# Peripheral.net
KiCad netlist of a schematic drawn in Altium Designer
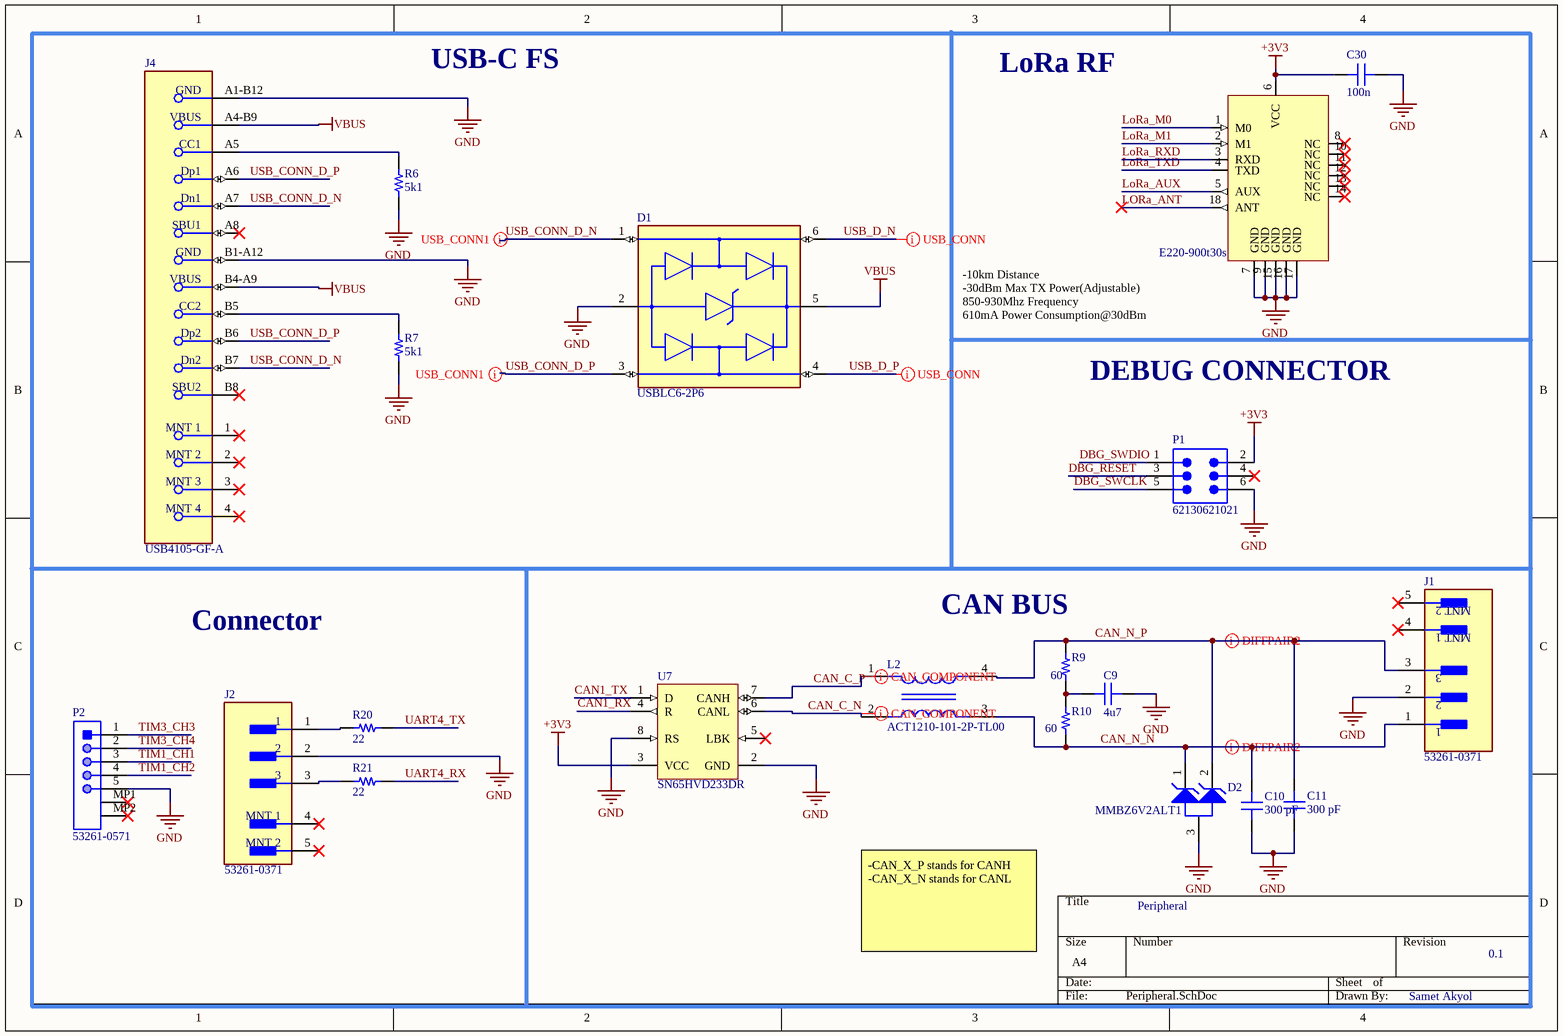
[diagram p0: Peripheral.SchDoc]

(export (version "E")
  (design (tool "Eeschema 10.0.6"))
  (components
    (comp (ref "C9")
      (value "4u7")
      (footprint "CAP 0603_1608")
      (description "CAP CER 4.7UF 25V X5R 0603")
      (fields
        (field (name "PART NUMBER") "CL10A475KA8NQNC")
        (field (name "MANUFACTURER") "Samsung Electro-Mechanics")
      )
      (libsource (lib "Celestial Altium Library - altium_library") (part "Capacitor"))
    )
    (comp (ref "C10")
      (value "300 pF")
      (footprint "CAP 0402_1005")
      (description "CAP CER 300PF 25V C0G/NP0 0402")
      (fields (field (name "PART NUMBER") "C0402C301J3GAC7867") (field (name "MANUFACTURER") "KEMET"))
      (libsource (lib "Celestial Altium Library - altium_library") (part "Capacitor"))
    )
    (comp (ref "C11")
      (value "300 pF")
      (footprint "CAP 0402_1005")
      (description "CAP CER 300PF 25V C0G/NP0 0402")
      (fields (field (name "PART NUMBER") "C0402C301J3GAC7867") (field (name "MANUFACTURER") "KEMET"))
      (libsource (lib "Celestial Altium Library - altium_library") (part "Capacitor"))
    )
    (comp (ref "C30")
      (value "100n")
      (footprint "CAP 0603_1608")
      (description "CAP CER 0.1UF 10V X7R 0603")
      (fields
        (field (name "PART NUMBER") "100X14W104MV4T")
        (field (name "MANUFACTURER") "Johanson Dielectrics Inc.")
      )
      (libsource (lib "Celestial Altium Library - altium_library") (part "Capacitor"))
    )
    (comp (ref "D1")
      (value "USBLC6-2P6")
      (footprint "FP-SOT-666-MFG")
      (description "TVS DIODE 5.25V 17V SOT666")
      (libsource (lib "Altium Content Vault") (part "c871e55f7e3243d341edbd671b98d92"))
    )
    (comp (ref "D2")
      (value "MMBZ6V2ALT1")
      (footprint "ONSC-SOT-23-3-318-08_V")
      (fields (field (name "MANUFACTURER") "On Semiconductor"))
      (libsource (lib "Altium Content Vault") (part "ONSC-K1K2A3-3"))
    )
    (comp (ref "J1")
      (value "53261-0371")
      (footprint "FP-53261-0371-MFG")
      (description "CONN HEADER SMD R/A 3POS 1.25MM")
      (fields
        (field (name "MANUFACTURER") "Molex")
        (field (name "OCTOPART") "https://octopart.com/53261-0371-molex-655314")
      )
      (libsource (lib "") (part "13850a6865a90496d8e6d51657cef87_1"))
    )
    (comp (ref "J2")
      (value "53261-0371")
      (footprint "FP-53261-0371-MFG")
      (description "CONN HEADER SMD R/A 3POS 1.25MM")
      (fields
        (field (name "MANUFACTURER") "Molex")
        (field (name "OCTOPART") "https://octopart.com/53261-0371-molex-655314")
      )
      (libsource (lib "Altium Content Vault") (part "13850a6865a90496d8e6d51657cef87"))
    )
    (comp (ref "J4")
      (value "USB4105-GF-A")
      (footprint "FP-USB4105-GF-A-MFG")
      (description "CONN RCPT USB2.0 TYPEC 5A")
      (fields
        (field (name "MANUFACTURER") "GCT")
        (field (name "OCTOPART") "https://octopart.com/usb4105-gf-a-gct-106627878")
      )
      (libsource (lib "Altium Content Vault") (part "e7c17a616881a82b79941196b4bec10"))
    )
    (comp (ref "L2")
      (value "ACT1210-101-2P-TL00")
      (footprint "FP-ACT1210-MFG")
      (description "CMC 100UH 150MA 2LN SMD AEC-Q200")
      (fields (field (name "TOLERANCE") "50%"))
      (libsource (lib "Altium Content Vault") (part "f3d33a36ca0ba39748c1b800686b6f9"))
    )
    (comp (ref "P1")
      (value "62130621021")
      (footprint "62130621021")
      (libsource (lib "Altium Content Vault") (part "Header_Male_2R_06P"))
    )
    (comp (ref "P2")
      (value "53261-0571")
      (footprint "MOLX-52361-0571-5_V")
      (description "Male Header, Pitch 1.25 mm, 1 x 5 Position, Height 3.4 mm, RoHS, Tape and Reel")
      (fields (field (name "MANUFACTURER") "Molex"))
      (libsource (lib "Altium Content Vault") (part "CN-1P-2M-R5"))
    )
    (comp (ref "R6")
      (value "5k1")
      (footprint "RES 0402_1005")
      (description "RES SMD 5.11KOHM 0.1% 1/16W 0402")
      (fields (field (name "PART NUMBER") "RT0402BRE075K11L") (field (name "MANUFACTURER") "Yageo"))
      (libsource (lib "Celestial Altium Library - altium_library") (part "Resistor"))
    )
    (comp (ref "R7")
      (value "5k1")
      (footprint "RES 0402_1005")
      (description "RES SMD 5.11KOHM 0.1% 1/16W 0402")
      (fields (field (name "PART NUMBER") "RT0402BRE075K11L") (field (name "MANUFACTURER") "Yageo"))
      (libsource (lib "Celestial Altium Library - altium_library") (part "Resistor"))
    )
    (comp (ref "R9")
      (value "60")
      (footprint "RES 0603_1608")
      (description "RES SMD 60.4 OHM 1% 1/10W 0603")
      (fields (field (name "PART NUMBER") "CR0603-FX-60R4ELF") (field (name "MANUFACTURER") "Bourns Inc."))
      (libsource (lib "Celestial Altium Library - altium_library") (part "Resistor"))
    )
    (comp (ref "R10")
      (value "60")
      (footprint "RES 0603_1608")
      (description "RES SMD 60.4 OHM 1% 1/10W 0603")
      (fields (field (name "PART NUMBER") "CR0603-FX-60R4ELF") (field (name "MANUFACTURER") "Bourns Inc."))
      (libsource (lib "Celestial Altium Library - altium_library") (part "Resistor"))
    )
    (comp (ref "R20")
      (value "22")
      (footprint "RES 0603_1608")
      (description "RES SMD 60.4 OHM 1% 1/10W 0603")
      (fields (field (name "PART NUMBER") "CR0603-FX-60R4ELF") (field (name "MANUFACTURER") "Bourns Inc."))
      (libsource (lib "Celestial Altium Library - altium_library") (part "Resistor"))
    )
    (comp (ref "R21")
      (value "22")
      (footprint "RES 0603_1608")
      (description "RES SMD 60.4 OHM 1% 1/10W 0603")
      (fields (field (name "PART NUMBER") "CR0603-FX-60R4ELF") (field (name "MANUFACTURER") "Bourns Inc."))
      (libsource (lib "Celestial Altium Library - altium_library") (part "Resistor"))
    )
    (comp (ref "U7")
      (value "SN65HVD233DR")
      (footprint "D0008A_M")
      (fields (field (name "MANUFACTURER") "Texas Instruments"))
      (libsource (lib "Altium Content Vault") (part "TI-SN65HVD233-SOIC_D-8"))
    )
    (comp (ref "U31")
      (value "E220-900t30s")
      (footprint "PE220-900T30S")
      (libsource (lib "E220") (part "E220-900"))
    )
  )
  (nets
    (net (code "1") (name "+3V3") (class "Default")
      (node (ref "C30") (pin "1") (pinfunction "1_1") (pintype "passive"))
      (node (ref "P1") (pin "2") (pinfunction "2_2") (pintype "passive"))
      (node (ref "U31") (pin "6") (pinfunction "VCC_6") (pintype "power_in"))
      (node (ref "U7") (pin "3") (pinfunction "VCC_3") (pintype "power_in"))
    )
    (net (code "2") (name "/CAN1_RX") (class "Default")
      (node (ref "U7") (pin "4") (pinfunction "R_4") (pintype "output"))
    )
    (net (code "3") (name "/CAN1_TX") (class "Default")
      (node (ref "U7") (pin "1") (pinfunction "D_1") (pintype "input"))
    )
    (net (code "4") (name "/CAN_C_N") (class "Default")
      (node (ref "L2") (pin "2") (pinfunction "2_2") (pintype "passive"))
      (node (ref "U7") (pin "6") (pinfunction "CANL_6") (pintype "bidirectional"))
    )
    (net (code "5") (name "/CAN_C_P") (class "Default")
      (node (ref "L2") (pin "1") (pinfunction "1_1") (pintype "passive"))
      (node (ref "U7") (pin "7") (pinfunction "CANH_7") (pintype "bidirectional"))
    )
    (net (code "6") (name "/CAN_N_N") (class "Default")
      (node (ref "C10") (pin "2") (pinfunction "2_2") (pintype "passive"))
      (node (ref "D2") (pin "1") (pinfunction "K1_1") (pintype "passive"))
      (node (ref "J1") (pin "1") (pinfunction "1_1") (pintype "passive"))
      (node (ref "L2") (pin "3") (pinfunction "3_3") (pintype "passive"))
      (node (ref "R10") (pin "1") (pinfunction "1_1") (pintype "passive"))
    )
    (net (code "7") (name "/CAN_N_P") (class "Default")
      (node (ref "C11") (pin "2") (pinfunction "2_2") (pintype "passive"))
      (node (ref "D2") (pin "2") (pinfunction "K2_2") (pintype "passive"))
      (node (ref "J1") (pin "3") (pinfunction "3_3") (pintype "passive"))
      (node (ref "L2") (pin "4") (pinfunction "4_4") (pintype "passive"))
      (node (ref "R9") (pin "2") (pinfunction "2_2") (pintype "passive"))
    )
    (net (code "8") (name "/DBG_RESET") (class "Default")
      (node (ref "P1") (pin "3") (pinfunction "3_3") (pintype "passive"))
    )
    (net (code "9") (name "/DBG_SWCLK") (class "Default")
      (node (ref "P1") (pin "5") (pinfunction "5_5") (pintype "passive"))
    )
    (net (code "10") (name "/DBG_SWDIO") (class "Default")
      (node (ref "P1") (pin "1") (pinfunction "1_1") (pintype "passive"))
    )
    (net (code "11") (name "/LORa_ANT") (class "Default")
      (node (ref "U31") (pin "18") (pinfunction "ANT_18") (pintype "output+no_connect"))
    )
    (net (code "12") (name "/LoRa_AUX") (class "Default")
      (node (ref "U31") (pin "5") (pinfunction "AUX_5") (pintype "output"))
    )
    (net (code "13") (name "/LoRa_M0") (class "Default")
      (node (ref "U31") (pin "1") (pinfunction "M0_1") (pintype "input"))
    )
    (net (code "14") (name "/LoRa_M1") (class "Default")
      (node (ref "U31") (pin "2") (pinfunction "M1_2") (pintype "input"))
    )
    (net (code "15") (name "/LoRa_RXD") (class "Default")
      (node (ref "U31") (pin "3") (pinfunction "RXD_3") (pintype "bidirectional"))
    )
    (net (code "16") (name "/LoRa_TXD") (class "Default")
      (node (ref "U31") (pin "4") (pinfunction "TXD_4") (pintype "bidirectional"))
    )
    (net (code "17") (name "/TIM1_CH1") (class "Default")
      (node (ref "P2") (pin "3") (pinfunction "3_3") (pintype "passive"))
    )
    (net (code "18") (name "/TIM1_CH2") (class "Default")
      (node (ref "P2") (pin "4") (pinfunction "4_4") (pintype "passive"))
    )
    (net (code "19") (name "/TIM3_CH3") (class "Default")
      (node (ref "P2") (pin "1") (pinfunction "1_1") (pintype "passive"))
    )
    (net (code "20") (name "/TIM3_CH4") (class "Default")
      (node (ref "P2") (pin "2") (pinfunction "2_2") (pintype "passive"))
    )
    (net (code "21") (name "/UART4_RX") (class "Default")
      (node (ref "R21") (pin "1") (pinfunction "1_1") (pintype "passive"))
    )
    (net (code "22") (name "/UART4_TX") (class "Default")
      (node (ref "R20") (pin "1") (pinfunction "1_1") (pintype "passive"))
    )
    (net (code "23") (name "/USB_CONN_D_N") (class "Default")
      (node (ref "D1") (pin "1") (pinfunction "I/O1_1") (pintype "bidirectional"))
      (node (ref "J4") (pin "A7") (pinfunction "Dn1_A7") (pintype "bidirectional"))
      (node (ref "J4") (pin "B7") (pinfunction "Dn2_B7") (pintype "bidirectional"))
    )
    (net (code "24") (name "/USB_CONN_D_P") (class "Default")
      (node (ref "D1") (pin "3") (pinfunction "I/O2_3") (pintype "bidirectional"))
      (node (ref "J4") (pin "A6") (pinfunction "Dp1_A6") (pintype "bidirectional"))
      (node (ref "J4") (pin "B6") (pinfunction "Dp2_B6") (pintype "bidirectional"))
    )
    (net (code "25") (name "/USB_D_N") (class "Default")
      (node (ref "D1") (pin "6") (pinfunction "I/O1_6") (pintype "bidirectional"))
    )
    (net (code "26") (name "/USB_D_P") (class "Default")
      (node (ref "D1") (pin "4") (pinfunction "I/O2_4") (pintype "bidirectional"))
    )
    (net (code "27") (name "GND") (class "Default")
      (node (ref "C10") (pin "1") (pinfunction "1_1") (pintype "passive"))
      (node (ref "C11") (pin "1") (pinfunction "1_1") (pintype "passive"))
      (node (ref "C30") (pin "2") (pinfunction "2_2") (pintype "passive"))
      (node (ref "C9") (pin "2") (pinfunction "2_2") (pintype "passive"))
      (node (ref "D1") (pin "2") (pinfunction "GND_2") (pintype "power_in"))
      (node (ref "D2") (pin "3") (pinfunction "A_3") (pintype "passive"))
      (node (ref "J1") (pin "2") (pinfunction "2_2") (pintype "passive"))
      (node (ref "J2") (pin "2") (pinfunction "2_2") (pintype "passive"))
      (node (ref "J4") (pin "A1-B12") (pinfunction "GND_A1-B12") (pintype "power_in"))
      (node (ref "J4") (pin "B1-A12") (pinfunction "GND_B1-A12") (pintype "bidirectional"))
      (node (ref "P1") (pin "6") (pinfunction "6_6") (pintype "passive"))
      (node (ref "P2") (pin "5") (pinfunction "5_5") (pintype "passive"))
      (node (ref "R6") (pin "1") (pinfunction "1_1") (pintype "passive"))
      (node (ref "R7") (pin "1") (pinfunction "1_1") (pintype "passive"))
      (node (ref "U31") (pin "15") (pinfunction "GND_15") (pintype "passive"))
      (node (ref "U31") (pin "16") (pinfunction "GND_16") (pintype "passive"))
      (node (ref "U31") (pin "17") (pinfunction "GND_17") (pintype "passive"))
      (node (ref "U31") (pin "7") (pinfunction "GND_7") (pintype "passive"))
      (node (ref "U31") (pin "9") (pinfunction "GND_9") (pintype "passive"))
      (node (ref "U7") (pin "2") (pinfunction "GND_2") (pintype "power_in"))
      (node (ref "U7") (pin "8") (pinfunction "RS_8") (pintype "input"))
    )
    (net (code "28") (name "Net-(C9-Pad1)") (class "Default")
      (node (ref "C9") (pin "1") (pinfunction "1_1") (pintype "passive"))
      (node (ref "R10") (pin "2") (pinfunction "2_2") (pintype "passive"))
      (node (ref "R9") (pin "1") (pinfunction "1_1") (pintype "passive"))
    )
    (net (code "29") (name "Net-(J2-Pad1)") (class "Default")
      (node (ref "J2") (pin "1") (pinfunction "1_1") (pintype "passive"))
      (node (ref "R20") (pin "2") (pinfunction "2_2") (pintype "passive"))
    )
    (net (code "30") (name "Net-(J2-Pad3)") (class "Default")
      (node (ref "J2") (pin "3") (pinfunction "3_3") (pintype "passive"))
      (node (ref "R21") (pin "2") (pinfunction "2_2") (pintype "passive"))
    )
    (net (code "31") (name "Net-(J4-CC1)") (class "Default")
      (node (ref "J4") (pin "A5") (pinfunction "CC1_A5") (pintype "power_in"))
      (node (ref "R6") (pin "2") (pinfunction "2_2") (pintype "passive"))
    )
    (net (code "32") (name "Net-(J4-CC2)") (class "Default")
      (node (ref "J4") (pin "B5") (pinfunction "CC2_B5") (pintype "bidirectional"))
      (node (ref "R7") (pin "2") (pinfunction "2_2") (pintype "passive"))
    )
    (net (code "33") (name "VBUS") (class "Default")
      (node (ref "D1") (pin "5") (pinfunction "VBUS_5") (pintype "power_in"))
      (node (ref "J4") (pin "A4-B9") (pinfunction "VBUS_A4-B9") (pintype "power_in"))
      (node (ref "J4") (pin "B4-A9") (pinfunction "VBUS_B4-A9") (pintype "bidirectional"))
    )
    (net (code "34") (name "unconnected-(J1-MNT_1-Pad4)") (class "Default")
      (node (ref "J1") (pin "4") (pinfunction "MNT_1_4") (pintype "passive+no_connect"))
    )
    (net (code "35") (name "unconnected-(J1-MNT_2-Pad5)") (class "Default")
      (node (ref "J1") (pin "5") (pinfunction "MNT_2_5") (pintype "passive+no_connect"))
    )
    (net (code "36") (name "unconnected-(J2-MNT_1-Pad4)") (class "Default")
      (node (ref "J2") (pin "4") (pinfunction "MNT_1_4") (pintype "passive+no_connect"))
    )
    (net (code "37") (name "unconnected-(J2-MNT_2-Pad5)") (class "Default")
      (node (ref "J2") (pin "5") (pinfunction "MNT_2_5") (pintype "passive+no_connect"))
    )
    (net (code "38") (name "unconnected-(J4-MNT_1-Pad1)") (class "Default")
      (node (ref "J4") (pin "1") (pinfunction "MNT_1_1") (pintype "power_in+no_connect"))
    )
    (net (code "39") (name "unconnected-(J4-MNT_2-Pad2)") (class "Default")
      (node (ref "J4") (pin "2") (pinfunction "MNT_2_2") (pintype "power_in+no_connect"))
    )
    (net (code "40") (name "unconnected-(J4-MNT_3-Pad3)") (class "Default")
      (node (ref "J4") (pin "3") (pinfunction "MNT_3_3") (pintype "power_in+no_connect"))
    )
    (net (code "41") (name "unconnected-(J4-MNT_4-Pad4)") (class "Default")
      (node (ref "J4") (pin "4") (pinfunction "MNT_4_4") (pintype "power_in+no_connect"))
    )
    (net (code "42") (name "unconnected-(J4-SBU1-PadA8)") (class "Default")
      (node (ref "J4") (pin "A8") (pinfunction "SBU1_A8") (pintype "bidirectional+no_connect"))
    )
    (net (code "43") (name "unconnected-(J4-SBU2-PadB8)") (class "Default")
      (node (ref "J4") (pin "B8") (pinfunction "SBU2_B8") (pintype "power_in+no_connect"))
    )
    (net (code "44") (name "unconnected-(P1-Pad4)") (class "Default")
      (node (ref "P1") (pin "4") (pinfunction "4_4") (pintype "passive+no_connect"))
    )
    (net (code "45") (name "unconnected-(P2-PadMP1)") (class "Default")
      (node (ref "P2") (pin "MP1") (pinfunction "MP1_MP1") (pintype "passive+no_connect"))
    )
    (net (code "46") (name "unconnected-(P2-PadMP2)") (class "Default")
      (node (ref "P2") (pin "MP2") (pinfunction "MP2_MP2") (pintype "passive+no_connect"))
    )
    (net (code "47") (name "unconnected-(U7-LBK-Pad5)") (class "Default")
      (node (ref "U7") (pin "5") (pinfunction "LBK_5") (pintype "input+no_connect"))
    )
    (net (code "48") (name "unconnected-(U31B-NC-Pad8)") (class "Default")
      (node (ref "U31") (pin "8") (pinfunction "NC_8") (pintype "passive+no_connect"))
    )
    (net (code "49") (name "unconnected-(U31B-NC-Pad10)") (class "Default")
      (node (ref "U31") (pin "10") (pinfunction "NC_10") (pintype "passive+no_connect"))
    )
    (net (code "50") (name "unconnected-(U31B-NC-Pad11)") (class "Default")
      (node (ref "U31") (pin "11") (pinfunction "NC_11") (pintype "passive+no_connect"))
    )
    (net (code "51") (name "unconnected-(U31B-NC-Pad12)") (class "Default")
      (node (ref "U31") (pin "12") (pinfunction "NC_12") (pintype "passive+no_connect"))
    )
    (net (code "52") (name "unconnected-(U31B-NC-Pad13)") (class "Default")
      (node (ref "U31") (pin "13") (pinfunction "NC_13") (pintype "passive+no_connect"))
    )
    (net (code "53") (name "unconnected-(U31B-NC-Pad14)") (class "Default")
      (node (ref "U31") (pin "14") (pinfunction "NC_14") (pintype "passive+no_connect"))
    )
  )
)
